# SCM-140-ADSR.net
KiCad netlist of a schematic drawn in EAGLE
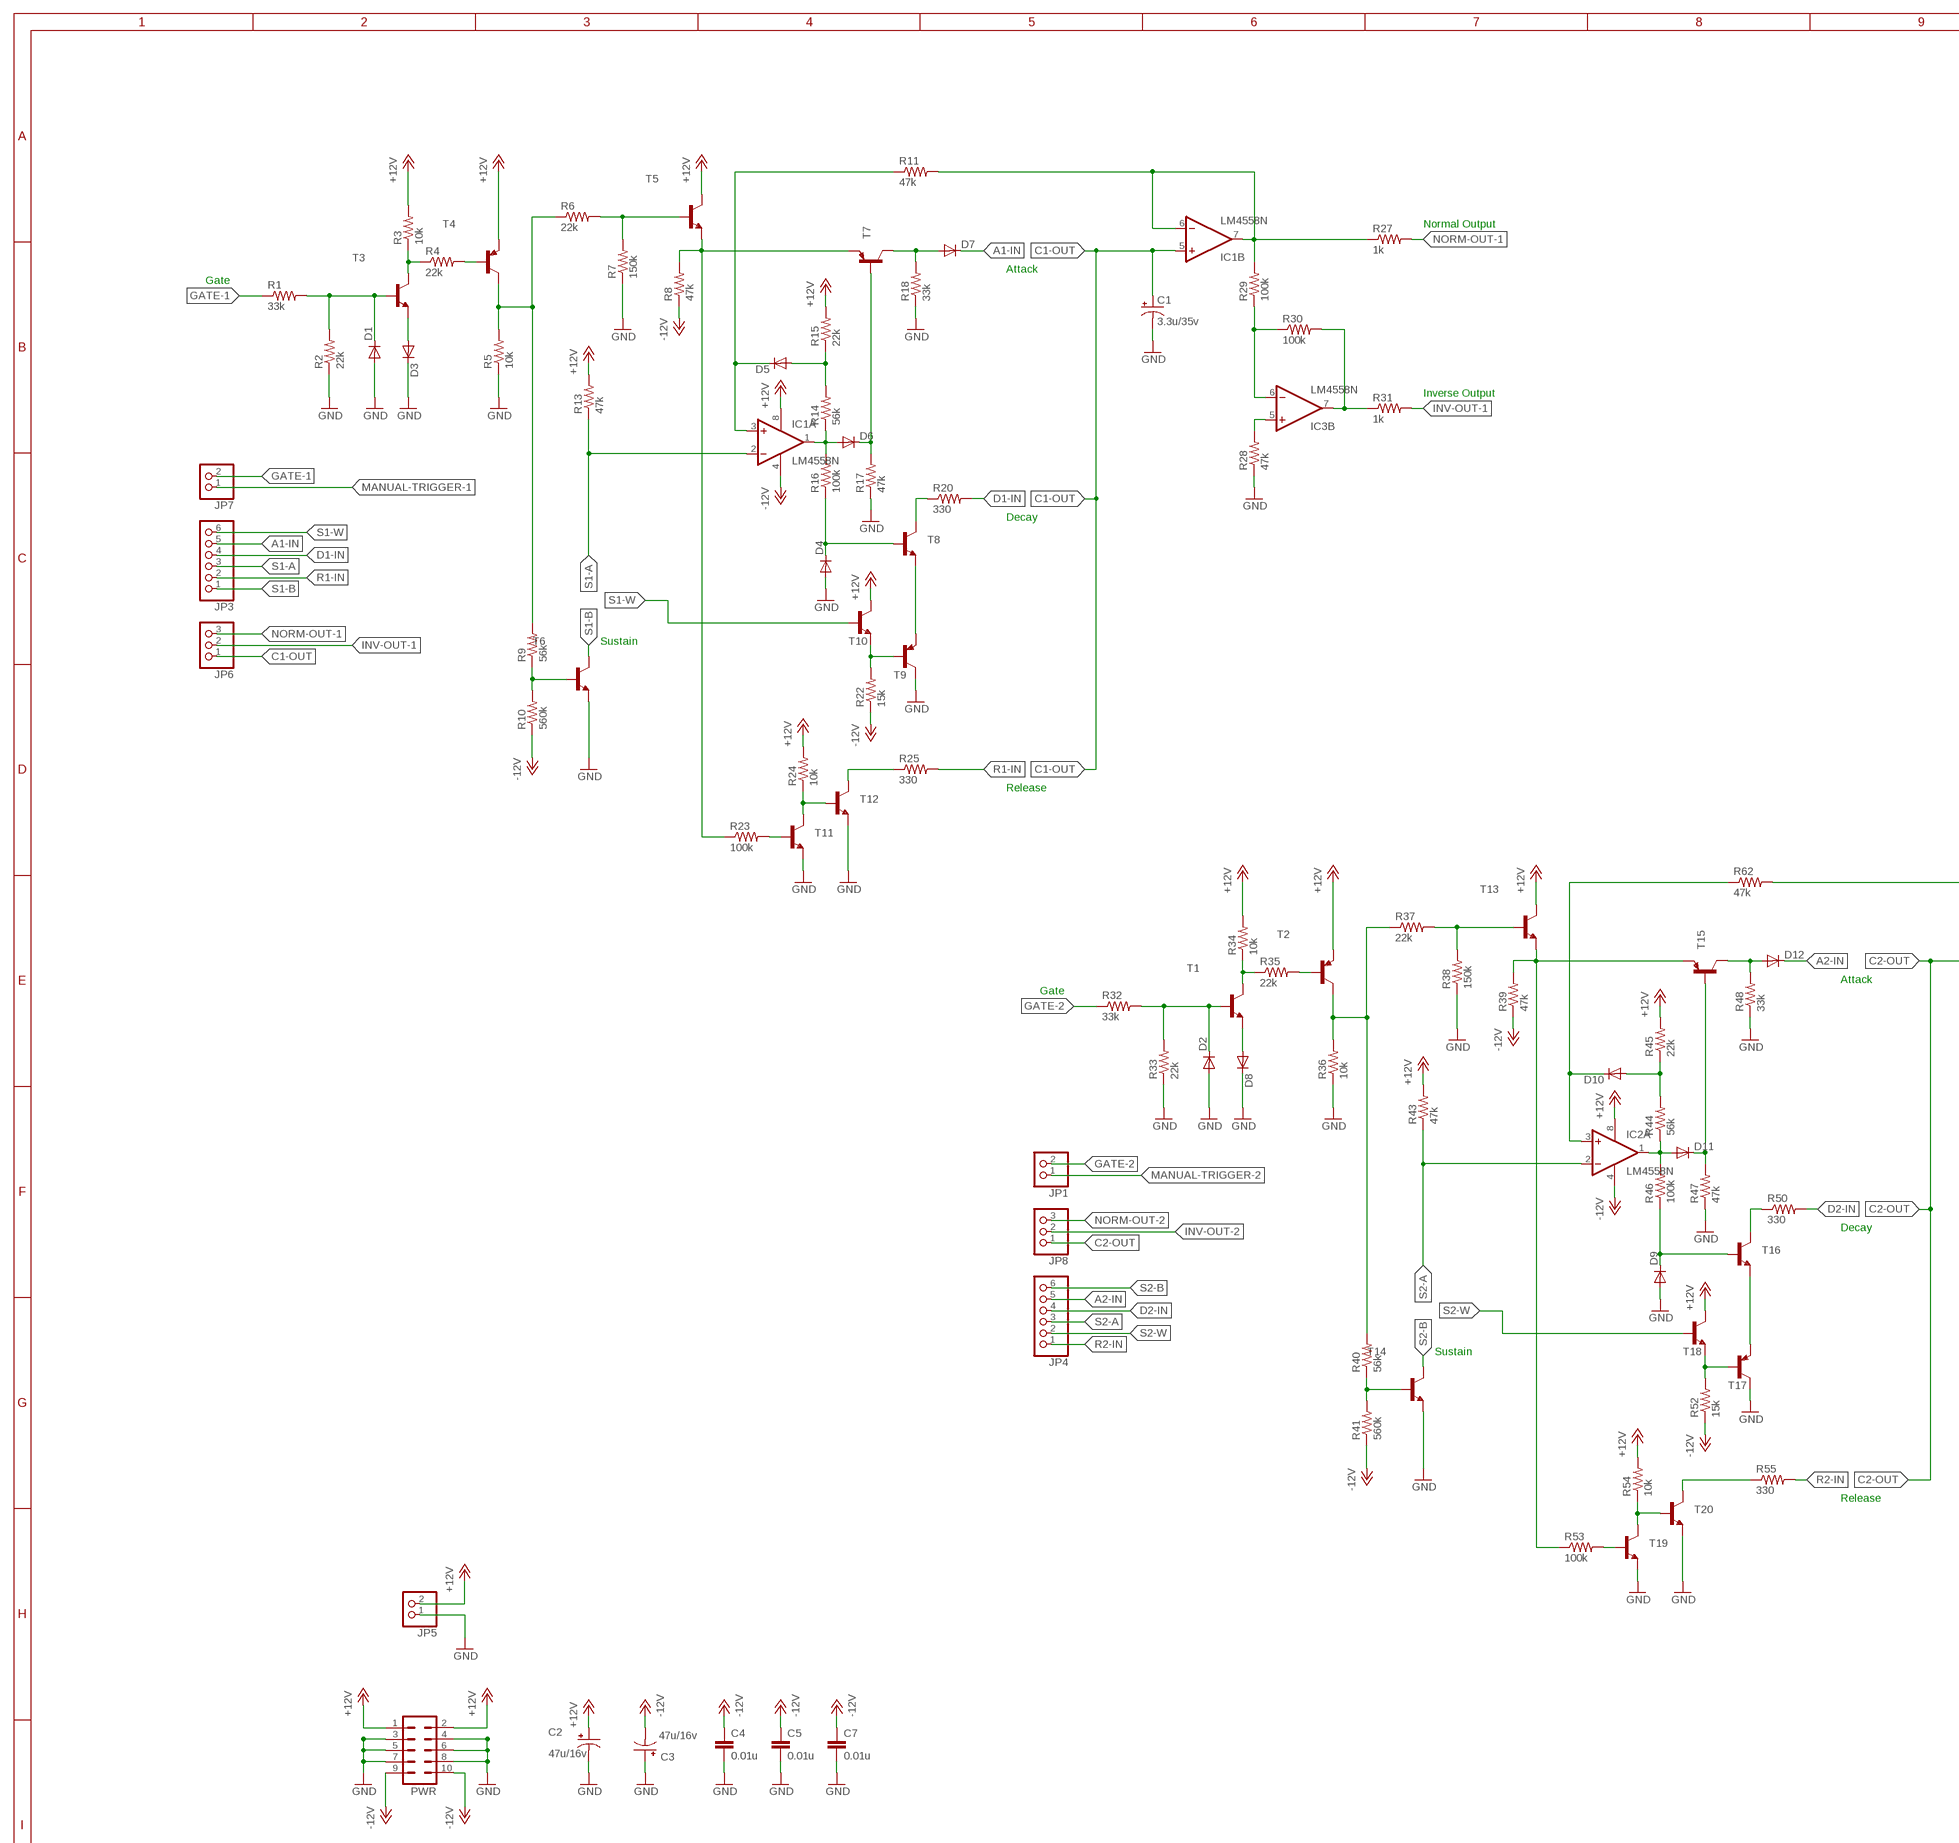
[diagram p0: schematic, sheet 1, part 1 of 2]
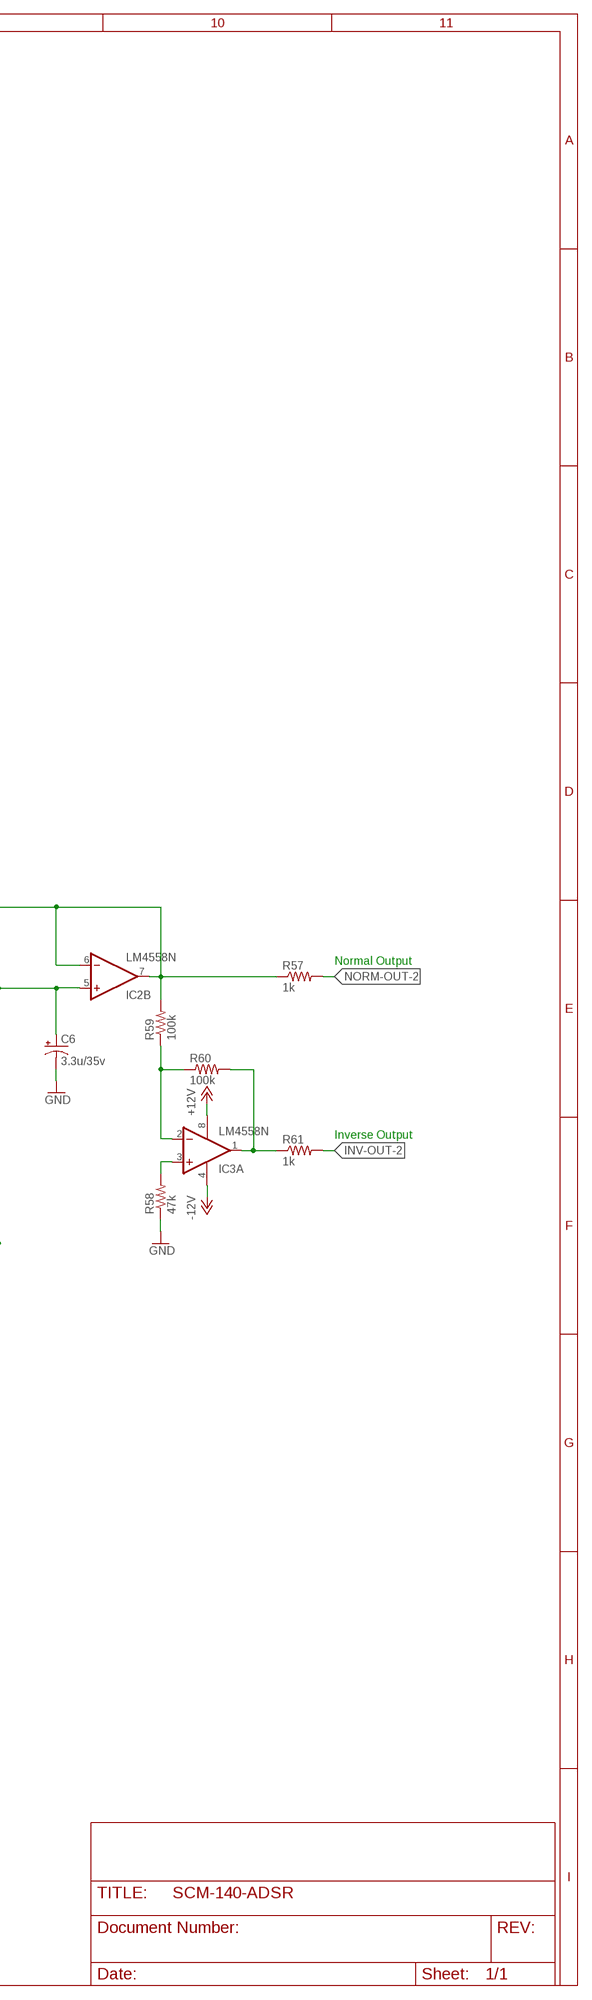
[diagram p1: schematic, sheet 1, part 2 of 2]

(export (version "E")
  (design (tool "Eeschema 10.0.6"))
  (components
    (comp (ref "C1")
      (value "3.3u/35v")
      (footprint "eagle-import:E2,5-5")
      (libsource (lib "eagle-import") (part "CPOL-USE2.5-5"))
    )
    (comp (ref "C2")
      (value "47u/16v")
      (footprint "eagle-import:E2,5-5")
      (libsource (lib "eagle-import") (part "CPOL-USE2.5-5"))
    )
    (comp (ref "C3")
      (value "47u/16v")
      (footprint "eagle-import:E2,5-5")
      (libsource (lib "eagle-import") (part "CPOL-USE2.5-5"))
    )
    (comp (ref "C4")
      (value "0.01u")
      (footprint "eagle-import:C025-024X044")
      (libsource (lib "eagle-import") (part "C-EU025-024X044"))
    )
    (comp (ref "C5")
      (value "0.01u")
      (footprint "eagle-import:C025-024X044")
      (libsource (lib "eagle-import") (part "C-EU025-024X044"))
    )
    (comp (ref "C6")
      (value "3.3u/35v")
      (footprint "eagle-import:E2,5-5")
      (libsource (lib "eagle-import") (part "CPOL-USE2.5-5"))
    )
    (comp (ref "C7")
      (value "0.01u")
      (footprint "eagle-import:C025-024X044")
      (libsource (lib "eagle-import") (part "C-EU025-024X044"))
    )
    (comp (ref "D1")
      (value "1N4148DO35-7")
      (footprint "eagle-import:DO35-7")
      (libsource (lib "eagle-import") (part "1N4148DO35-7"))
    )
    (comp (ref "D2")
      (value "1N4148DO35-7")
      (footprint "eagle-import:DO35-7")
      (libsource (lib "eagle-import") (part "1N4148DO35-7"))
    )
    (comp (ref "D3")
      (value "1N4148DO35-7")
      (footprint "eagle-import:DO35-7")
      (libsource (lib "eagle-import") (part "1N4148DO35-7"))
    )
    (comp (ref "D4")
      (value "1N4148DO35-7")
      (footprint "eagle-import:DO35-7")
      (libsource (lib "eagle-import") (part "1N4148DO35-7"))
    )
    (comp (ref "D5")
      (value "1N4148DO35-7")
      (footprint "eagle-import:DO35-7")
      (libsource (lib "eagle-import") (part "1N4148DO35-7"))
    )
    (comp (ref "D6")
      (value "1N4148DO35-7")
      (footprint "eagle-import:DO35-7")
      (libsource (lib "eagle-import") (part "1N4148DO35-7"))
    )
    (comp (ref "D7")
      (value "1N4148DO35-7")
      (footprint "eagle-import:DO35-7")
      (libsource (lib "eagle-import") (part "1N4148DO35-7"))
    )
    (comp (ref "D8")
      (value "1N4148DO35-7")
      (footprint "eagle-import:DO35-7")
      (libsource (lib "eagle-import") (part "1N4148DO35-7"))
    )
    (comp (ref "D9")
      (value "1N4148DO35-7")
      (footprint "eagle-import:DO35-7")
      (libsource (lib "eagle-import") (part "1N4148DO35-7"))
    )
    (comp (ref "D10")
      (value "1N4148DO35-7")
      (footprint "eagle-import:DO35-7")
      (libsource (lib "eagle-import") (part "1N4148DO35-7"))
    )
    (comp (ref "D11")
      (value "1N4148DO35-7")
      (footprint "eagle-import:DO35-7")
      (libsource (lib "eagle-import") (part "1N4148DO35-7"))
    )
    (comp (ref "D12")
      (value "1N4148DO35-7")
      (footprint "eagle-import:DO35-7")
      (libsource (lib "eagle-import") (part "1N4148DO35-7"))
    )
    (comp (ref "IC1")
      (value "LM4558N")
      (footprint "eagle-import:DIL08")
      (libsource (lib "eagle-import") (part "4558NLM"))
    )
    (comp (ref "IC2")
      (value "LM4558N")
      (footprint "eagle-import:DIL08")
      (libsource (lib "eagle-import") (part "4558NLM"))
    )
    (comp (ref "IC3")
      (value "LM4558N")
      (footprint "eagle-import:DIL08")
      (libsource (lib "eagle-import") (part "4558NLM"))
    )
    (comp (ref "JP1")
      (value "PINHD-1X2")
      (footprint "eagle-import:1X02")
      (libsource (lib "eagle-import") (part "PINHD-1X2"))
    )
    (comp (ref "JP3")
      (value "PINHD-1X6")
      (footprint "eagle-import:1X06")
      (libsource (lib "eagle-import") (part "PINHD-1X6"))
    )
    (comp (ref "JP4")
      (value "PINHD-1X6")
      (footprint "eagle-import:1X06")
      (libsource (lib "eagle-import") (part "PINHD-1X6"))
    )
    (comp (ref "JP5")
      (value "PINHD-1X2")
      (footprint "eagle-import:1X02")
      (libsource (lib "eagle-import") (part "PINHD-1X2"))
    )
    (comp (ref "JP6")
      (value "PINHD-1X3")
      (footprint "eagle-import:1X03")
      (libsource (lib "eagle-import") (part "PINHD-1X3"))
    )
    (comp (ref "JP7")
      (value "PINHD-1X2")
      (footprint "eagle-import:1X02")
      (libsource (lib "eagle-import") (part "PINHD-1X2"))
    )
    (comp (ref "JP8")
      (value "PINHD-1X3")
      (footprint "eagle-import:1X03")
      (libsource (lib "eagle-import") (part "PINHD-1X3"))
    )
    (comp (ref "PWR")
      (value "ML10")
      (footprint "eagle-import:ML10")
      (libsource (lib "eagle-import") (part "ML10"))
    )
    (comp (ref "R1")
      (value "33k")
      (footprint "eagle-import:0204_7")
      (libsource (lib "eagle-import") (part "R-US_0204/7"))
    )
    (comp (ref "R2")
      (value "22k")
      (footprint "eagle-import:0204_7")
      (libsource (lib "eagle-import") (part "R-US_0204/7"))
    )
    (comp (ref "R3")
      (value "10k")
      (footprint "eagle-import:0204_7")
      (libsource (lib "eagle-import") (part "R-US_0204/7"))
    )
    (comp (ref "R4")
      (value "22k")
      (footprint "eagle-import:0204_7")
      (libsource (lib "eagle-import") (part "R-US_0204/7"))
    )
    (comp (ref "R5")
      (value "10k")
      (footprint "eagle-import:0204_7")
      (libsource (lib "eagle-import") (part "R-US_0204/7"))
    )
    (comp (ref "R6")
      (value "22k")
      (footprint "eagle-import:0204_7")
      (libsource (lib "eagle-import") (part "R-US_0204/7"))
    )
    (comp (ref "R7")
      (value "150k")
      (footprint "eagle-import:0204_7")
      (libsource (lib "eagle-import") (part "R-US_0204/7"))
    )
    (comp (ref "R8")
      (value "47k")
      (footprint "eagle-import:0204_7")
      (libsource (lib "eagle-import") (part "R-US_0204/7"))
    )
    (comp (ref "R9")
      (value "56k")
      (footprint "eagle-import:0204_7")
      (libsource (lib "eagle-import") (part "R-US_0204/7"))
    )
    (comp (ref "R10")
      (value "560k")
      (footprint "eagle-import:0204_7")
      (libsource (lib "eagle-import") (part "R-US_0204/7"))
    )
    (comp (ref "R11")
      (value "47k")
      (footprint "eagle-import:0204_7")
      (libsource (lib "eagle-import") (part "R-US_0204/7"))
    )
    (comp (ref "R13")
      (value "47k")
      (footprint "eagle-import:0204_7")
      (libsource (lib "eagle-import") (part "R-US_0204/7"))
    )
    (comp (ref "R14")
      (value "56k")
      (footprint "eagle-import:0204_7")
      (libsource (lib "eagle-import") (part "R-US_0204/7"))
    )
    (comp (ref "R15")
      (value "22k")
      (footprint "eagle-import:0204_7")
      (libsource (lib "eagle-import") (part "R-US_0204/7"))
    )
    (comp (ref "R16")
      (value "100k")
      (footprint "eagle-import:0204_7")
      (libsource (lib "eagle-import") (part "R-US_0204/7"))
    )
    (comp (ref "R17")
      (value "47k")
      (footprint "eagle-import:0204_7")
      (libsource (lib "eagle-import") (part "R-US_0204/7"))
    )
    (comp (ref "R18")
      (value "33k")
      (footprint "eagle-import:0204_7")
      (libsource (lib "eagle-import") (part "R-US_0204/7"))
    )
    (comp (ref "R20")
      (value "330")
      (footprint "eagle-import:0204_7")
      (libsource (lib "eagle-import") (part "R-US_0204/7"))
    )
    (comp (ref "R22")
      (value "15k")
      (footprint "eagle-import:0204_7")
      (libsource (lib "eagle-import") (part "R-US_0204/7"))
    )
    (comp (ref "R23")
      (value "100k")
      (footprint "eagle-import:0204_7")
      (libsource (lib "eagle-import") (part "R-US_0204/7"))
    )
    (comp (ref "R24")
      (value "10k")
      (footprint "eagle-import:0204_7")
      (libsource (lib "eagle-import") (part "R-US_0204/7"))
    )
    (comp (ref "R25")
      (value "330")
      (footprint "eagle-import:0204_7")
      (libsource (lib "eagle-import") (part "R-US_0204/7"))
    )
    (comp (ref "R27")
      (value "1k")
      (footprint "eagle-import:0204_7")
      (libsource (lib "eagle-import") (part "R-US_0204/7"))
    )
    (comp (ref "R28")
      (value "47k")
      (footprint "eagle-import:0204_7")
      (libsource (lib "eagle-import") (part "R-US_0204/7"))
    )
    (comp (ref "R29")
      (value "100k")
      (footprint "eagle-import:0204_7")
      (libsource (lib "eagle-import") (part "R-US_0204/7"))
    )
    (comp (ref "R30")
      (value "100k")
      (footprint "eagle-import:0204_7")
      (libsource (lib "eagle-import") (part "R-US_0204/7"))
    )
    (comp (ref "R31")
      (value "1k")
      (footprint "eagle-import:0204_7")
      (libsource (lib "eagle-import") (part "R-US_0204/7"))
    )
    (comp (ref "R32")
      (value "33k")
      (footprint "eagle-import:0204_7")
      (libsource (lib "eagle-import") (part "R-US_0204/7"))
    )
    (comp (ref "R33")
      (value "22k")
      (footprint "eagle-import:0204_7")
      (libsource (lib "eagle-import") (part "R-US_0204/7"))
    )
    (comp (ref "R34")
      (value "10k")
      (footprint "eagle-import:0204_7")
      (libsource (lib "eagle-import") (part "R-US_0204/7"))
    )
    (comp (ref "R35")
      (value "22k")
      (footprint "eagle-import:0204_7")
      (libsource (lib "eagle-import") (part "R-US_0204/7"))
    )
    (comp (ref "R36")
      (value "10k")
      (footprint "eagle-import:0204_7")
      (libsource (lib "eagle-import") (part "R-US_0204/7"))
    )
    (comp (ref "R37")
      (value "22k")
      (footprint "eagle-import:0204_7")
      (libsource (lib "eagle-import") (part "R-US_0204/7"))
    )
    (comp (ref "R38")
      (value "150k")
      (footprint "eagle-import:0204_7")
      (libsource (lib "eagle-import") (part "R-US_0204/7"))
    )
    (comp (ref "R39")
      (value "47k")
      (footprint "eagle-import:0204_7")
      (libsource (lib "eagle-import") (part "R-US_0204/7"))
    )
    (comp (ref "R40")
      (value "56k")
      (footprint "eagle-import:0204_7")
      (libsource (lib "eagle-import") (part "R-US_0204/7"))
    )
    (comp (ref "R41")
      (value "560k")
      (footprint "eagle-import:0204_7")
      (libsource (lib "eagle-import") (part "R-US_0204/7"))
    )
    (comp (ref "R43")
      (value "47k")
      (footprint "eagle-import:0204_7")
      (libsource (lib "eagle-import") (part "R-US_0204/7"))
    )
    (comp (ref "R44")
      (value "56k")
      (footprint "eagle-import:0204_7")
      (libsource (lib "eagle-import") (part "R-US_0204/7"))
    )
    (comp (ref "R45")
      (value "22k")
      (footprint "eagle-import:0204_7")
      (libsource (lib "eagle-import") (part "R-US_0204/7"))
    )
    (comp (ref "R46")
      (value "100k")
      (footprint "eagle-import:0204_7")
      (libsource (lib "eagle-import") (part "R-US_0204/7"))
    )
    (comp (ref "R47")
      (value "47k")
      (footprint "eagle-import:0204_7")
      (libsource (lib "eagle-import") (part "R-US_0204/7"))
    )
    (comp (ref "R48")
      (value "33k")
      (footprint "eagle-import:0204_7")
      (libsource (lib "eagle-import") (part "R-US_0204/7"))
    )
    (comp (ref "R50")
      (value "330")
      (footprint "eagle-import:0204_7")
      (libsource (lib "eagle-import") (part "R-US_0204/7"))
    )
    (comp (ref "R52")
      (value "15k")
      (footprint "eagle-import:0204_7")
      (libsource (lib "eagle-import") (part "R-US_0204/7"))
    )
    (comp (ref "R53")
      (value "100k")
      (footprint "eagle-import:0204_7")
      (libsource (lib "eagle-import") (part "R-US_0204/7"))
    )
    (comp (ref "R54")
      (value "10k")
      (footprint "eagle-import:0204_7")
      (libsource (lib "eagle-import") (part "R-US_0204/7"))
    )
    (comp (ref "R55")
      (value "330")
      (footprint "eagle-import:0204_7")
      (libsource (lib "eagle-import") (part "R-US_0204/7"))
    )
    (comp (ref "R57")
      (value "1k")
      (footprint "eagle-import:0204_7")
      (libsource (lib "eagle-import") (part "R-US_0204/7"))
    )
    (comp (ref "R58")
      (value "47k")
      (footprint "eagle-import:0204_7")
      (libsource (lib "eagle-import") (part "R-US_0204/7"))
    )
    (comp (ref "R59")
      (value "100k")
      (footprint "eagle-import:0204_7")
      (libsource (lib "eagle-import") (part "R-US_0204/7"))
    )
    (comp (ref "R60")
      (value "100k")
      (footprint "eagle-import:0204_7")
      (libsource (lib "eagle-import") (part "R-US_0204/7"))
    )
    (comp (ref "R61")
      (value "1k")
      (footprint "eagle-import:0204_7")
      (libsource (lib "eagle-import") (part "R-US_0204/7"))
    )
    (comp (ref "R62")
      (value "47k")
      (footprint "eagle-import:0204_7")
      (libsource (lib "eagle-import") (part "R-US_0204/7"))
    )
    (comp (ref "T1")
      (value "BC547B-NPN-TO92-CBE")
      (footprint "eagle-import:TO92-CBE")
      (libsource (lib "eagle-import") (part "-NPN-TO92-CBEBC547B"))
    )
    (comp (ref "T2")
      (value "BC557B-PNP-TO92-EBC")
      (footprint "eagle-import:TO92-EBC")
      (libsource (lib "eagle-import") (part "-PNP-TO92-EBCBC557B"))
    )
    (comp (ref "T3")
      (value "BC547B-NPN-TO92-CBE")
      (footprint "eagle-import:TO92-CBE")
      (libsource (lib "eagle-import") (part "-NPN-TO92-CBEBC547B"))
    )
    (comp (ref "T4")
      (value "BC557B-PNP-TO92-EBC")
      (footprint "eagle-import:TO92-EBC")
      (libsource (lib "eagle-import") (part "-PNP-TO92-EBCBC557B"))
    )
    (comp (ref "T5")
      (value "BC547B-NPN-TO92-CBE")
      (footprint "eagle-import:TO92-CBE")
      (libsource (lib "eagle-import") (part "-NPN-TO92-CBEBC547B"))
    )
    (comp (ref "T6")
      (value "BC547B-NPN-TO92-CBE")
      (footprint "eagle-import:TO92-CBE")
      (libsource (lib "eagle-import") (part "-NPN-TO92-CBEBC547B"))
    )
    (comp (ref "T7")
      (value "BC557B-PNP-TO92-EBC")
      (footprint "eagle-import:TO92-EBC")
      (libsource (lib "eagle-import") (part "-PNP-TO92-EBCBC557B"))
    )
    (comp (ref "T8")
      (value "BC547B-NPN-TO92-CBE")
      (footprint "eagle-import:TO92-CBE")
      (libsource (lib "eagle-import") (part "-NPN-TO92-CBEBC547B"))
    )
    (comp (ref "T9")
      (value "BC557B-PNP-TO92-EBC")
      (footprint "eagle-import:TO92-EBC")
      (libsource (lib "eagle-import") (part "-PNP-TO92-EBCBC557B"))
    )
    (comp (ref "T10")
      (value "BC547B-NPN-TO92-CBE")
      (footprint "eagle-import:TO92-CBE")
      (libsource (lib "eagle-import") (part "-NPN-TO92-CBEBC547B"))
    )
    (comp (ref "T11")
      (value "BC547B-NPN-TO92-CBE")
      (footprint "eagle-import:TO92-CBE")
      (libsource (lib "eagle-import") (part "-NPN-TO92-CBEBC547B"))
    )
    (comp (ref "T12")
      (value "BC547B-NPN-TO92-CBE")
      (footprint "eagle-import:TO92-CBE")
      (libsource (lib "eagle-import") (part "-NPN-TO92-CBEBC547B"))
    )
    (comp (ref "T13")
      (value "BC547B-NPN-TO92-CBE")
      (footprint "eagle-import:TO92-CBE")
      (libsource (lib "eagle-import") (part "-NPN-TO92-CBEBC547B"))
    )
    (comp (ref "T14")
      (value "BC547B-NPN-TO92-CBE")
      (footprint "eagle-import:TO92-CBE")
      (libsource (lib "eagle-import") (part "-NPN-TO92-CBEBC547B"))
    )
    (comp (ref "T15")
      (value "BC557B-PNP-TO92-EBC")
      (footprint "eagle-import:TO92-EBC")
      (libsource (lib "eagle-import") (part "-PNP-TO92-EBCBC557B"))
    )
    (comp (ref "T16")
      (value "BC547B-NPN-TO92-CBE")
      (footprint "eagle-import:TO92-CBE")
      (libsource (lib "eagle-import") (part "-NPN-TO92-CBEBC547B"))
    )
    (comp (ref "T17")
      (value "BC557B-PNP-TO92-EBC")
      (footprint "eagle-import:TO92-EBC")
      (libsource (lib "eagle-import") (part "-PNP-TO92-EBCBC557B"))
    )
    (comp (ref "T18")
      (value "BC547B-NPN-TO92-CBE")
      (footprint "eagle-import:TO92-CBE")
      (libsource (lib "eagle-import") (part "-NPN-TO92-CBEBC547B"))
    )
    (comp (ref "T19")
      (value "BC547B-NPN-TO92-CBE")
      (footprint "eagle-import:TO92-CBE")
      (libsource (lib "eagle-import") (part "-NPN-TO92-CBEBC547B"))
    )
    (comp (ref "T20")
      (value "BC547B-NPN-TO92-CBE")
      (footprint "eagle-import:TO92-CBE")
      (libsource (lib "eagle-import") (part "-NPN-TO92-CBEBC547B"))
    )
  )
  (nets
    (net (code "1") (name "+12V") (class "Default")
      (node (ref "C2") (pin "+") (pinfunction "+_+") (pintype "passive"))
      (node (ref "IC1") (pin "8") (pinfunction "V+_8") (pintype "power_in"))
      (node (ref "IC2") (pin "8") (pinfunction "V+_8") (pintype "power_in"))
      (node (ref "IC3") (pin "8") (pinfunction "V+_8") (pintype "power_in"))
      (node (ref "JP5") (pin "2") (pinfunction "2_2") (pintype "passive"))
      (node (ref "PWR") (pin "1") (pinfunction "1_1") (pintype "passive"))
      (node (ref "PWR") (pin "2") (pinfunction "2_2") (pintype "passive"))
      (node (ref "R13") (pin "2") (pinfunction "2_2") (pintype "passive"))
      (node (ref "R15") (pin "2") (pinfunction "2_2") (pintype "passive"))
      (node (ref "R24") (pin "2") (pinfunction "2_2") (pintype "passive"))
      (node (ref "R3") (pin "2") (pinfunction "2_2") (pintype "passive"))
      (node (ref "R34") (pin "2") (pinfunction "2_2") (pintype "passive"))
      (node (ref "R43") (pin "2") (pinfunction "2_2") (pintype "passive"))
      (node (ref "R45") (pin "2") (pinfunction "2_2") (pintype "passive"))
      (node (ref "R54") (pin "2") (pinfunction "2_2") (pintype "passive"))
      (node (ref "T10") (pin "C") (pinfunction "C_C") (pintype "passive"))
      (node (ref "T13") (pin "C") (pinfunction "C_C") (pintype "passive"))
      (node (ref "T18") (pin "C") (pinfunction "C_C") (pintype "passive"))
      (node (ref "T2") (pin "E") (pinfunction "E_E") (pintype "passive"))
      (node (ref "T4") (pin "E") (pinfunction "E_E") (pintype "passive"))
      (node (ref "T5") (pin "C") (pinfunction "C_C") (pintype "passive"))
    )
    (net (code "2") (name "-12V") (class "Default")
      (node (ref "C3") (pin "-") (pinfunction "-_-") (pintype "passive"))
      (node (ref "C4") (pin "1") (pinfunction "1_1") (pintype "passive"))
      (node (ref "C5") (pin "1") (pinfunction "1_1") (pintype "passive"))
      (node (ref "C7") (pin "1") (pinfunction "1_1") (pintype "passive"))
      (node (ref "IC1") (pin "4") (pinfunction "V-_4") (pintype "power_in"))
      (node (ref "IC2") (pin "4") (pinfunction "V-_4") (pintype "power_in"))
      (node (ref "IC3") (pin "4") (pinfunction "V-_4") (pintype "power_in"))
      (node (ref "PWR") (pin "10") (pinfunction "10_10") (pintype "passive"))
      (node (ref "PWR") (pin "9") (pinfunction "9_9") (pintype "passive"))
      (node (ref "R10") (pin "1") (pinfunction "1_1") (pintype "passive"))
      (node (ref "R22") (pin "1") (pinfunction "1_1") (pintype "passive"))
      (node (ref "R39") (pin "1") (pinfunction "1_1") (pintype "passive"))
      (node (ref "R41") (pin "1") (pinfunction "1_1") (pintype "passive"))
      (node (ref "R52") (pin "1") (pinfunction "1_1") (pintype "passive"))
      (node (ref "R8") (pin "1") (pinfunction "1_1") (pintype "passive"))
    )
    (net (code "3") (name "A1-IN") (class "Default")
      (node (ref "D7") (pin "C") (pinfunction "C_C") (pintype "passive"))
      (node (ref "JP3") (pin "5") (pinfunction "5_5") (pintype "passive"))
    )
    (net (code "4") (name "A2-IN") (class "Default")
      (node (ref "D12") (pin "C") (pinfunction "C_C") (pintype "passive"))
      (node (ref "JP4") (pin "5") (pinfunction "5_5") (pintype "passive"))
    )
    (net (code "5") (name "C1-OUT") (class "Default")
      (node (ref "C1") (pin "+") (pinfunction "+_+") (pintype "passive"))
      (node (ref "IC1") (pin "5") (pinfunction "+IN_5") (pintype "input"))
      (node (ref "JP6") (pin "1") (pinfunction "1_1") (pintype "passive"))
    )
    (net (code "6") (name "C2-OUT") (class "Default")
      (node (ref "C6") (pin "+") (pinfunction "+_+") (pintype "passive"))
      (node (ref "IC2") (pin "5") (pinfunction "+IN_5") (pintype "input"))
      (node (ref "JP8") (pin "1") (pinfunction "1_1") (pintype "passive"))
    )
    (net (code "7") (name "D1-IN") (class "Default")
      (node (ref "JP3") (pin "4") (pinfunction "4_4") (pintype "passive"))
      (node (ref "R20") (pin "2") (pinfunction "2_2") (pintype "passive"))
    )
    (net (code "8") (name "D2-IN") (class "Default")
      (node (ref "JP4") (pin "4") (pinfunction "4_4") (pintype "passive"))
      (node (ref "R50") (pin "2") (pinfunction "2_2") (pintype "passive"))
    )
    (net (code "9") (name "GATE-1") (class "Default")
      (node (ref "JP7") (pin "2") (pinfunction "2_2") (pintype "passive"))
      (node (ref "R1") (pin "1") (pinfunction "1_1") (pintype "passive"))
    )
    (net (code "10") (name "GATE-2") (class "Default")
      (node (ref "JP1") (pin "2") (pinfunction "2_2") (pintype "passive"))
      (node (ref "R32") (pin "1") (pinfunction "1_1") (pintype "passive"))
    )
    (net (code "11") (name "GND") (class "Default")
      (node (ref "C1") (pin "-") (pinfunction "-_-") (pintype "passive"))
      (node (ref "C2") (pin "-") (pinfunction "-_-") (pintype "passive"))
      (node (ref "C3") (pin "+") (pinfunction "+_+") (pintype "passive"))
      (node (ref "C4") (pin "2") (pinfunction "2_2") (pintype "passive"))
      (node (ref "C5") (pin "2") (pinfunction "2_2") (pintype "passive"))
      (node (ref "C6") (pin "-") (pinfunction "-_-") (pintype "passive"))
      (node (ref "C7") (pin "2") (pinfunction "2_2") (pintype "passive"))
      (node (ref "D1") (pin "A") (pinfunction "A_A") (pintype "passive"))
      (node (ref "D2") (pin "A") (pinfunction "A_A") (pintype "passive"))
      (node (ref "D3") (pin "C") (pinfunction "C_C") (pintype "passive"))
      (node (ref "D4") (pin "A") (pinfunction "A_A") (pintype "passive"))
      (node (ref "D8") (pin "C") (pinfunction "C_C") (pintype "passive"))
      (node (ref "D9") (pin "A") (pinfunction "A_A") (pintype "passive"))
      (node (ref "JP5") (pin "1") (pinfunction "1_1") (pintype "passive"))
      (node (ref "PWR") (pin "3") (pinfunction "3_3") (pintype "passive"))
      (node (ref "PWR") (pin "4") (pinfunction "4_4") (pintype "passive"))
      (node (ref "PWR") (pin "5") (pinfunction "5_5") (pintype "passive"))
      (node (ref "PWR") (pin "6") (pinfunction "6_6") (pintype "passive"))
      (node (ref "PWR") (pin "7") (pinfunction "7_7") (pintype "passive"))
      (node (ref "PWR") (pin "8") (pinfunction "8_8") (pintype "passive"))
      (node (ref "R17") (pin "1") (pinfunction "1_1") (pintype "passive"))
      (node (ref "R18") (pin "1") (pinfunction "1_1") (pintype "passive"))
      (node (ref "R2") (pin "1") (pinfunction "1_1") (pintype "passive"))
      (node (ref "R28") (pin "1") (pinfunction "1_1") (pintype "passive"))
      (node (ref "R33") (pin "1") (pinfunction "1_1") (pintype "passive"))
      (node (ref "R36") (pin "1") (pinfunction "1_1") (pintype "passive"))
      (node (ref "R38") (pin "1") (pinfunction "1_1") (pintype "passive"))
      (node (ref "R47") (pin "1") (pinfunction "1_1") (pintype "passive"))
      (node (ref "R48") (pin "1") (pinfunction "1_1") (pintype "passive"))
      (node (ref "R5") (pin "1") (pinfunction "1_1") (pintype "passive"))
      (node (ref "R58") (pin "1") (pinfunction "1_1") (pintype "passive"))
      (node (ref "R7") (pin "1") (pinfunction "1_1") (pintype "passive"))
      (node (ref "T11") (pin "E") (pinfunction "E_E") (pintype "passive"))
      (node (ref "T12") (pin "E") (pinfunction "E_E") (pintype "passive"))
      (node (ref "T14") (pin "E") (pinfunction "E_E") (pintype "passive"))
      (node (ref "T17") (pin "C") (pinfunction "C_C") (pintype "passive"))
      (node (ref "T19") (pin "E") (pinfunction "E_E") (pintype "passive"))
      (node (ref "T20") (pin "E") (pinfunction "E_E") (pintype "passive"))
      (node (ref "T6") (pin "E") (pinfunction "E_E") (pintype "passive"))
      (node (ref "T9") (pin "C") (pinfunction "C_C") (pintype "passive"))
    )
    (net (code "12") (name "INV-OUT-1") (class "Default")
      (node (ref "JP6") (pin "2") (pinfunction "2_2") (pintype "passive"))
      (node (ref "R31") (pin "2") (pinfunction "2_2") (pintype "passive"))
    )
    (net (code "13") (name "INV-OUT-2") (class "Default")
      (node (ref "JP8") (pin "2") (pinfunction "2_2") (pintype "passive"))
      (node (ref "R61") (pin "2") (pinfunction "2_2") (pintype "passive"))
    )
    (net (code "14") (name "MANUAL-TRIGGER-1") (class "Default")
      (node (ref "D1") (pin "C") (pinfunction "C_C") (pintype "passive"))
      (node (ref "JP7") (pin "1") (pinfunction "1_1") (pintype "passive"))
      (node (ref "R1") (pin "2") (pinfunction "2_2") (pintype "passive"))
      (node (ref "R2") (pin "2") (pinfunction "2_2") (pintype "passive"))
      (node (ref "T3") (pin "B") (pinfunction "B_B") (pintype "passive"))
    )
    (net (code "15") (name "MANUAL-TRIGGER-2") (class "Default")
      (node (ref "D2") (pin "C") (pinfunction "C_C") (pintype "passive"))
      (node (ref "JP1") (pin "1") (pinfunction "1_1") (pintype "passive"))
      (node (ref "R32") (pin "2") (pinfunction "2_2") (pintype "passive"))
      (node (ref "R33") (pin "2") (pinfunction "2_2") (pintype "passive"))
      (node (ref "T1") (pin "B") (pinfunction "B_B") (pintype "passive"))
    )
    (net (code "16") (name "NORM-OUT-1") (class "Default")
      (node (ref "JP6") (pin "3") (pinfunction "3_3") (pintype "passive"))
      (node (ref "R27") (pin "2") (pinfunction "2_2") (pintype "passive"))
    )
    (net (code "17") (name "NORM-OUT-2") (class "Default")
      (node (ref "JP8") (pin "3") (pinfunction "3_3") (pintype "passive"))
      (node (ref "R57") (pin "2") (pinfunction "2_2") (pintype "passive"))
    )
    (net (code "18") (name "Net-(D3-PadA)") (class "Default")
      (node (ref "D3") (pin "A") (pinfunction "A_A") (pintype "passive"))
      (node (ref "T3") (pin "E") (pinfunction "E_E") (pintype "passive"))
    )
    (net (code "19") (name "Net-(D4-PadC)") (class "Default")
      (node (ref "D4") (pin "C") (pinfunction "C_C") (pintype "passive"))
      (node (ref "R16") (pin "1") (pinfunction "1_1") (pintype "passive"))
      (node (ref "T8") (pin "B") (pinfunction "B_B") (pintype "passive"))
    )
    (net (code "20") (name "Net-(D5-PadA)") (class "Default")
      (node (ref "D5") (pin "A") (pinfunction "A_A") (pintype "passive"))
      (node (ref "R14") (pin "2") (pinfunction "2_2") (pintype "passive"))
      (node (ref "R15") (pin "1") (pinfunction "1_1") (pintype "passive"))
    )
    (net (code "21") (name "Net-(D6-PadC)") (class "Default")
      (node (ref "D6") (pin "C") (pinfunction "C_C") (pintype "passive"))
      (node (ref "R17") (pin "2") (pinfunction "2_2") (pintype "passive"))
      (node (ref "T7") (pin "B") (pinfunction "B_B") (pintype "passive"))
    )
    (net (code "22") (name "Net-(D7-PadA)") (class "Default")
      (node (ref "D7") (pin "A") (pinfunction "A_A") (pintype "passive"))
      (node (ref "R18") (pin "2") (pinfunction "2_2") (pintype "passive"))
      (node (ref "T7") (pin "C") (pinfunction "C_C") (pintype "passive"))
    )
    (net (code "23") (name "Net-(D8-PadA)") (class "Default")
      (node (ref "D8") (pin "A") (pinfunction "A_A") (pintype "passive"))
      (node (ref "T1") (pin "E") (pinfunction "E_E") (pintype "passive"))
    )
    (net (code "24") (name "Net-(D9-PadC)") (class "Default")
      (node (ref "D9") (pin "C") (pinfunction "C_C") (pintype "passive"))
      (node (ref "R46") (pin "1") (pinfunction "1_1") (pintype "passive"))
      (node (ref "T16") (pin "B") (pinfunction "B_B") (pintype "passive"))
    )
    (net (code "25") (name "Net-(D10-PadA)") (class "Default")
      (node (ref "D10") (pin "A") (pinfunction "A_A") (pintype "passive"))
      (node (ref "R44") (pin "2") (pinfunction "2_2") (pintype "passive"))
      (node (ref "R45") (pin "1") (pinfunction "1_1") (pintype "passive"))
    )
    (net (code "26") (name "Net-(D11-PadC)") (class "Default")
      (node (ref "D11") (pin "C") (pinfunction "C_C") (pintype "passive"))
      (node (ref "R47") (pin "2") (pinfunction "2_2") (pintype "passive"))
      (node (ref "T15") (pin "B") (pinfunction "B_B") (pintype "passive"))
    )
    (net (code "27") (name "Net-(D12-PadA)") (class "Default")
      (node (ref "D12") (pin "A") (pinfunction "A_A") (pintype "passive"))
      (node (ref "R48") (pin "2") (pinfunction "2_2") (pintype "passive"))
      (node (ref "T15") (pin "C") (pinfunction "C_C") (pintype "passive"))
    )
    (net (code "28") (name "Net-(IC1A-+IN)") (class "Default")
      (node (ref "D5") (pin "C") (pinfunction "C_C") (pintype "passive"))
      (node (ref "IC1") (pin "3") (pinfunction "+IN_3") (pintype "input"))
      (node (ref "R11") (pin "1") (pinfunction "1_1") (pintype "passive"))
    )
    (net (code "29") (name "Net-(IC1A-OUT)") (class "Default")
      (node (ref "D6") (pin "A") (pinfunction "A_A") (pintype "passive"))
      (node (ref "IC1") (pin "1") (pinfunction "OUT_1") (pintype "output"))
      (node (ref "R14") (pin "1") (pinfunction "1_1") (pintype "passive"))
      (node (ref "R16") (pin "2") (pinfunction "2_2") (pintype "passive"))
    )
    (net (code "30") (name "Net-(IC1B--IN)") (class "Default")
      (node (ref "IC1") (pin "6") (pinfunction "-IN_6") (pintype "input"))
      (node (ref "IC1") (pin "7") (pinfunction "OUT_7") (pintype "output"))
      (node (ref "R11") (pin "2") (pinfunction "2_2") (pintype "passive"))
      (node (ref "R27") (pin "1") (pinfunction "1_1") (pintype "passive"))
      (node (ref "R29") (pin "2") (pinfunction "2_2") (pintype "passive"))
    )
    (net (code "31") (name "Net-(IC2A-+IN)") (class "Default")
      (node (ref "D10") (pin "C") (pinfunction "C_C") (pintype "passive"))
      (node (ref "IC2") (pin "3") (pinfunction "+IN_3") (pintype "input"))
      (node (ref "R62") (pin "1") (pinfunction "1_1") (pintype "passive"))
    )
    (net (code "32") (name "Net-(IC2A-OUT)") (class "Default")
      (node (ref "D11") (pin "A") (pinfunction "A_A") (pintype "passive"))
      (node (ref "IC2") (pin "1") (pinfunction "OUT_1") (pintype "output"))
      (node (ref "R44") (pin "1") (pinfunction "1_1") (pintype "passive"))
      (node (ref "R46") (pin "2") (pinfunction "2_2") (pintype "passive"))
    )
    (net (code "33") (name "Net-(IC2B--IN)") (class "Default")
      (node (ref "IC2") (pin "6") (pinfunction "-IN_6") (pintype "input"))
      (node (ref "IC2") (pin "7") (pinfunction "OUT_7") (pintype "output"))
      (node (ref "R57") (pin "1") (pinfunction "1_1") (pintype "passive"))
      (node (ref "R59") (pin "2") (pinfunction "2_2") (pintype "passive"))
      (node (ref "R62") (pin "2") (pinfunction "2_2") (pintype "passive"))
    )
    (net (code "34") (name "Net-(IC3A-+IN)") (class "Default")
      (node (ref "IC3") (pin "3") (pinfunction "+IN_3") (pintype "input"))
      (node (ref "R58") (pin "2") (pinfunction "2_2") (pintype "passive"))
    )
    (net (code "35") (name "Net-(IC3A--IN)") (class "Default")
      (node (ref "IC3") (pin "2") (pinfunction "-IN_2") (pintype "input"))
      (node (ref "R59") (pin "1") (pinfunction "1_1") (pintype "passive"))
      (node (ref "R60") (pin "1") (pinfunction "1_1") (pintype "passive"))
    )
    (net (code "36") (name "Net-(IC3A-OUT)") (class "Default")
      (node (ref "IC3") (pin "1") (pinfunction "OUT_1") (pintype "output"))
      (node (ref "R60") (pin "2") (pinfunction "2_2") (pintype "passive"))
      (node (ref "R61") (pin "1") (pinfunction "1_1") (pintype "passive"))
    )
    (net (code "37") (name "Net-(IC3B-+IN)") (class "Default")
      (node (ref "IC3") (pin "5") (pinfunction "+IN_5") (pintype "input"))
      (node (ref "R28") (pin "2") (pinfunction "2_2") (pintype "passive"))
    )
    (net (code "38") (name "Net-(IC3B--IN)") (class "Default")
      (node (ref "IC3") (pin "6") (pinfunction "-IN_6") (pintype "input"))
      (node (ref "R29") (pin "1") (pinfunction "1_1") (pintype "passive"))
      (node (ref "R30") (pin "1") (pinfunction "1_1") (pintype "passive"))
    )
    (net (code "39") (name "Net-(IC3B-OUT)") (class "Default")
      (node (ref "IC3") (pin "7") (pinfunction "OUT_7") (pintype "output"))
      (node (ref "R30") (pin "2") (pinfunction "2_2") (pintype "passive"))
      (node (ref "R31") (pin "1") (pinfunction "1_1") (pintype "passive"))
    )
    (net (code "40") (name "Net-(R3-Pad1)") (class "Default")
      (node (ref "R3") (pin "1") (pinfunction "1_1") (pintype "passive"))
      (node (ref "R4") (pin "1") (pinfunction "1_1") (pintype "passive"))
      (node (ref "T3") (pin "C") (pinfunction "C_C") (pintype "passive"))
    )
    (net (code "41") (name "Net-(R4-Pad2)") (class "Default")
      (node (ref "R4") (pin "2") (pinfunction "2_2") (pintype "passive"))
      (node (ref "T4") (pin "B") (pinfunction "B_B") (pintype "passive"))
    )
    (net (code "42") (name "Net-(R5-Pad2)") (class "Default")
      (node (ref "R5") (pin "2") (pinfunction "2_2") (pintype "passive"))
      (node (ref "R6") (pin "1") (pinfunction "1_1") (pintype "passive"))
      (node (ref "R9") (pin "2") (pinfunction "2_2") (pintype "passive"))
      (node (ref "T4") (pin "C") (pinfunction "C_C") (pintype "passive"))
    )
    (net (code "43") (name "Net-(R6-Pad2)") (class "Default")
      (node (ref "R6") (pin "2") (pinfunction "2_2") (pintype "passive"))
      (node (ref "R7") (pin "2") (pinfunction "2_2") (pintype "passive"))
      (node (ref "T5") (pin "B") (pinfunction "B_B") (pintype "passive"))
    )
    (net (code "44") (name "Net-(R10-Pad2)") (class "Default")
      (node (ref "R10") (pin "2") (pinfunction "2_2") (pintype "passive"))
      (node (ref "R9") (pin "1") (pinfunction "1_1") (pintype "passive"))
      (node (ref "T6") (pin "B") (pinfunction "B_B") (pintype "passive"))
    )
    (net (code "45") (name "Net-(R20-Pad1)") (class "Default")
      (node (ref "R20") (pin "1") (pinfunction "1_1") (pintype "passive"))
      (node (ref "T8") (pin "C") (pinfunction "C_C") (pintype "passive"))
    )
    (net (code "46") (name "Net-(R22-Pad2)") (class "Default")
      (node (ref "R22") (pin "2") (pinfunction "2_2") (pintype "passive"))
      (node (ref "T10") (pin "E") (pinfunction "E_E") (pintype "passive"))
      (node (ref "T9") (pin "B") (pinfunction "B_B") (pintype "passive"))
    )
    (net (code "47") (name "Net-(R23-Pad1)") (class "Default")
      (node (ref "R23") (pin "1") (pinfunction "1_1") (pintype "passive"))
      (node (ref "R8") (pin "2") (pinfunction "2_2") (pintype "passive"))
      (node (ref "T5") (pin "E") (pinfunction "E_E") (pintype "passive"))
      (node (ref "T7") (pin "E") (pinfunction "E_E") (pintype "passive"))
    )
    (net (code "48") (name "Net-(R23-Pad2)") (class "Default")
      (node (ref "R23") (pin "2") (pinfunction "2_2") (pintype "passive"))
      (node (ref "T11") (pin "B") (pinfunction "B_B") (pintype "passive"))
    )
    (net (code "49") (name "Net-(R24-Pad1)") (class "Default")
      (node (ref "R24") (pin "1") (pinfunction "1_1") (pintype "passive"))
      (node (ref "T11") (pin "C") (pinfunction "C_C") (pintype "passive"))
      (node (ref "T12") (pin "B") (pinfunction "B_B") (pintype "passive"))
    )
    (net (code "50") (name "Net-(R25-Pad1)") (class "Default")
      (node (ref "R25") (pin "1") (pinfunction "1_1") (pintype "passive"))
      (node (ref "T12") (pin "C") (pinfunction "C_C") (pintype "passive"))
    )
    (net (code "51") (name "Net-(R34-Pad1)") (class "Default")
      (node (ref "R34") (pin "1") (pinfunction "1_1") (pintype "passive"))
      (node (ref "R35") (pin "1") (pinfunction "1_1") (pintype "passive"))
      (node (ref "T1") (pin "C") (pinfunction "C_C") (pintype "passive"))
    )
    (net (code "52") (name "Net-(R35-Pad2)") (class "Default")
      (node (ref "R35") (pin "2") (pinfunction "2_2") (pintype "passive"))
      (node (ref "T2") (pin "B") (pinfunction "B_B") (pintype "passive"))
    )
    (net (code "53") (name "Net-(R36-Pad2)") (class "Default")
      (node (ref "R36") (pin "2") (pinfunction "2_2") (pintype "passive"))
      (node (ref "R37") (pin "1") (pinfunction "1_1") (pintype "passive"))
      (node (ref "R40") (pin "2") (pinfunction "2_2") (pintype "passive"))
      (node (ref "T2") (pin "C") (pinfunction "C_C") (pintype "passive"))
    )
    (net (code "54") (name "Net-(R37-Pad2)") (class "Default")
      (node (ref "R37") (pin "2") (pinfunction "2_2") (pintype "passive"))
      (node (ref "R38") (pin "2") (pinfunction "2_2") (pintype "passive"))
      (node (ref "T13") (pin "B") (pinfunction "B_B") (pintype "passive"))
    )
    (net (code "55") (name "Net-(R39-Pad2)") (class "Default")
      (node (ref "R39") (pin "2") (pinfunction "2_2") (pintype "passive"))
      (node (ref "R53") (pin "1") (pinfunction "1_1") (pintype "passive"))
      (node (ref "T13") (pin "E") (pinfunction "E_E") (pintype "passive"))
      (node (ref "T15") (pin "E") (pinfunction "E_E") (pintype "passive"))
    )
    (net (code "56") (name "Net-(R40-Pad1)") (class "Default")
      (node (ref "R40") (pin "1") (pinfunction "1_1") (pintype "passive"))
      (node (ref "R41") (pin "2") (pinfunction "2_2") (pintype "passive"))
      (node (ref "T14") (pin "B") (pinfunction "B_B") (pintype "passive"))
    )
    (net (code "57") (name "Net-(R50-Pad1)") (class "Default")
      (node (ref "R50") (pin "1") (pinfunction "1_1") (pintype "passive"))
      (node (ref "T16") (pin "C") (pinfunction "C_C") (pintype "passive"))
    )
    (net (code "58") (name "Net-(R52-Pad2)") (class "Default")
      (node (ref "R52") (pin "2") (pinfunction "2_2") (pintype "passive"))
      (node (ref "T17") (pin "B") (pinfunction "B_B") (pintype "passive"))
      (node (ref "T18") (pin "E") (pinfunction "E_E") (pintype "passive"))
    )
    (net (code "59") (name "Net-(R53-Pad2)") (class "Default")
      (node (ref "R53") (pin "2") (pinfunction "2_2") (pintype "passive"))
      (node (ref "T19") (pin "B") (pinfunction "B_B") (pintype "passive"))
    )
    (net (code "60") (name "Net-(R54-Pad1)") (class "Default")
      (node (ref "R54") (pin "1") (pinfunction "1_1") (pintype "passive"))
      (node (ref "T19") (pin "C") (pinfunction "C_C") (pintype "passive"))
      (node (ref "T20") (pin "B") (pinfunction "B_B") (pintype "passive"))
    )
    (net (code "61") (name "Net-(R55-Pad1)") (class "Default")
      (node (ref "R55") (pin "1") (pinfunction "1_1") (pintype "passive"))
      (node (ref "T20") (pin "C") (pinfunction "C_C") (pintype "passive"))
    )
    (net (code "62") (name "Net-(T8-PadE)") (class "Default")
      (node (ref "T8") (pin "E") (pinfunction "E_E") (pintype "passive"))
      (node (ref "T9") (pin "E") (pinfunction "E_E") (pintype "passive"))
    )
    (net (code "63") (name "Net-(T16-PadE)") (class "Default")
      (node (ref "T16") (pin "E") (pinfunction "E_E") (pintype "passive"))
      (node (ref "T17") (pin "E") (pinfunction "E_E") (pintype "passive"))
    )
    (net (code "64") (name "R1-IN") (class "Default")
      (node (ref "JP3") (pin "2") (pinfunction "2_2") (pintype "passive"))
      (node (ref "R25") (pin "2") (pinfunction "2_2") (pintype "passive"))
    )
    (net (code "65") (name "R2-IN") (class "Default")
      (node (ref "JP4") (pin "1") (pinfunction "1_1") (pintype "passive"))
      (node (ref "R55") (pin "2") (pinfunction "2_2") (pintype "passive"))
    )
    (net (code "66") (name "S1-A") (class "Default")
      (node (ref "IC1") (pin "2") (pinfunction "-IN_2") (pintype "input"))
      (node (ref "JP3") (pin "3") (pinfunction "3_3") (pintype "passive"))
      (node (ref "R13") (pin "1") (pinfunction "1_1") (pintype "passive"))
    )
    (net (code "67") (name "S1-B") (class "Default")
      (node (ref "JP3") (pin "1") (pinfunction "1_1") (pintype "passive"))
      (node (ref "T6") (pin "C") (pinfunction "C_C") (pintype "passive"))
    )
    (net (code "68") (name "S1-W") (class "Default")
      (node (ref "JP3") (pin "6") (pinfunction "6_6") (pintype "passive"))
      (node (ref "T10") (pin "B") (pinfunction "B_B") (pintype "passive"))
    )
    (net (code "69") (name "S2-A") (class "Default")
      (node (ref "IC2") (pin "2") (pinfunction "-IN_2") (pintype "input"))
      (node (ref "JP4") (pin "3") (pinfunction "3_3") (pintype "passive"))
      (node (ref "R43") (pin "1") (pinfunction "1_1") (pintype "passive"))
    )
    (net (code "70") (name "S2-B") (class "Default")
      (node (ref "JP4") (pin "6") (pinfunction "6_6") (pintype "passive"))
      (node (ref "T14") (pin "C") (pinfunction "C_C") (pintype "passive"))
    )
    (net (code "71") (name "S2-W") (class "Default")
      (node (ref "JP4") (pin "2") (pinfunction "2_2") (pintype "passive"))
      (node (ref "T18") (pin "B") (pinfunction "B_B") (pintype "passive"))
    )
  )
)
